# YTN1-POWER1-RoHS.net
KiCad netlist of a schematic drawn in Altium Designer
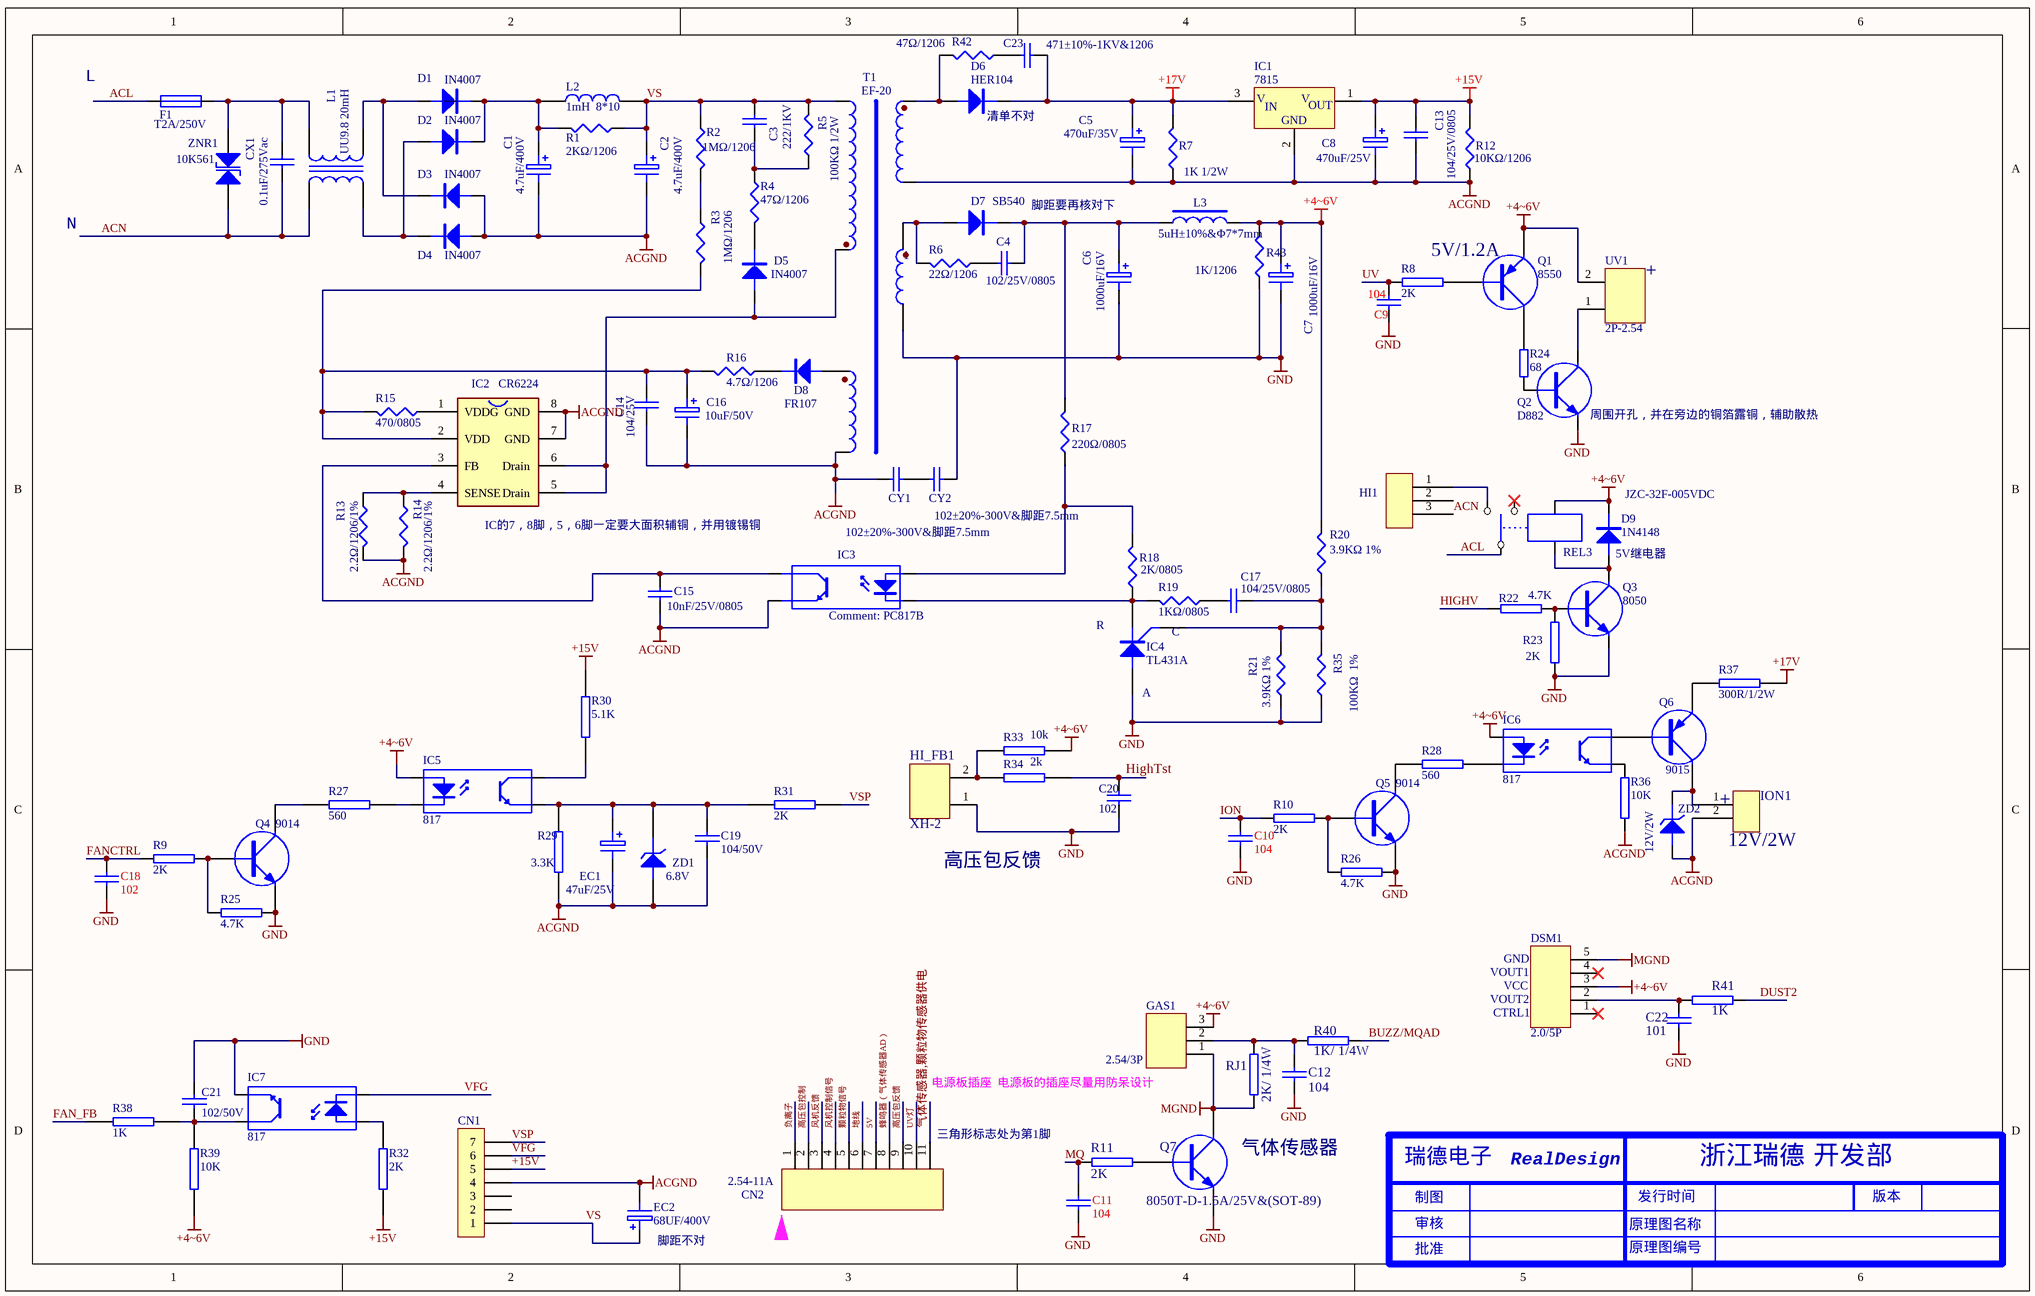
[diagram p0: YTN1-POWER1-RoHS.schdoc]

(export (version "E")
  (design (tool "Eeschema 10.0.6"))
  (components
    (comp (ref "1") (value "~") (libsource (lib "*") (part "INDUCTOR")))
    (comp (ref "C1") (value "4.7uF/400V") (libsource (lib "*") (part "Pro18.tmp_150uF/400V_45")))
    (comp (ref "C2") (value "4.7uF/400V") (libsource (lib "*") (part "Pro18.tmp_150uF/400V_45")))
    (comp (ref "C3") (value "222/1KV") (libsource (lib "*") (part "Pro18.tmp_103M/50V_42")))
    (comp (ref "C4") (value "102/25V/0805") (libsource (lib "*") (part "Pro18.tmp_104M/50V_1")))
    (comp (ref "C5")
      (value "470uF/35V")
      (footprint "ESR")
      (libsource (lib "*") (part "Pro18.tmp_1KuF/16V_17"))
    )
    (comp (ref "C6")
      (value "1000uF/16V")
      (footprint "ESR")
      (libsource (lib "*") (part "Pro18.tmp_1KuF/16V_17"))
    )
    (comp (ref "C7")
      (value "1000uF/16V")
      (footprint "ESR")
      (libsource (lib "*") (part "Pro18.tmp_1KuF/16V_17"))
    )
    (comp (ref "C8")
      (value "470uF/25V")
      (footprint "ESR")
      (libsource (lib "*") (part "Pro18.tmp_1KuF/16V_17"))
    )
    (comp (ref "C9")
      (value "104")
      (footprint "C104")
      (description "瓷片电容、独石电容")
      (libsource (lib "") (part "CAP_1"))
    )
    (comp (ref "C10")
      (value "104")
      (footprint "C104")
      (description "瓷片电容、独石电容")
      (libsource (lib "") (part "CAP_1"))
    )
    (comp (ref "C11")
      (value "104")
      (footprint "C104")
      (description "瓷片电容、独石电容")
      (libsource (lib "") (part "CAP_1"))
    )
    (comp (ref "C12")
      (value "104")
      (footprint "0805C")
      (description "瓷片电容、独石电容")
      (libsource (lib "") (part "CAP_1"))
    )
    (comp (ref "C13") (value "104/25V/0805") (libsource (lib "*") (part "Pro18.tmp_104M/50V_1")))
    (comp (ref "C14") (value "104/25V") (libsource (lib "*") (part "Pro18.tmp_103M/50V_42")))
    (comp (ref "C15") (value "10nF/25V/0805") (libsource (lib "*") (part "Pro18.tmp_103M/50V_42")))
    (comp (ref "C16") (value "10uF/50V") (libsource (lib "*") (part "Pro18.tmp_100uF/35V_31")))
    (comp (ref "C17") (value "104/25V/0805") (libsource (lib "*") (part "Pro18.tmp_103M/50V_42")))
    (comp (ref "C18")
      (value "102")
      (footprint "C104")
      (description "瓷片电容、独石电容")
      (libsource (lib "") (part "CAP_1"))
    )
    (comp (ref "C19")
      (value "104/50V")
      (footprint "0805C")
      (description "Capacitor")
      (libsource (lib "*") (part "CAP"))
    )
    (comp (ref "C20") (value "102") (footprint "0805C") (libsource (lib "") (part "CAP_1")))
    (comp (ref "C21")
      (value "102/50V")
      (footprint "0805C")
      (description "Capacitor")
      (libsource (lib "*") (part "CAP"))
    )
    (comp (ref "C22")
      (value "101")
      (footprint "0805C")
      (description "瓷片电容、独石电容")
      (libsource (lib "") (part "CAP_1"))
    )
    (comp (ref "C23") (value "471±10%-1KV&1206") (libsource (lib "*") (part "Pro18.tmp_104M/50V_1")))
    (comp (ref "CN1")
      (value "~")
      (footprint "XH-7AW")
      (description "Connector")
      (libsource (lib "*") (part "CON7"))
    )
    (comp (ref "CN2") (value "2.54-11A") (footprint "xh-12aw") (libsource (lib "*") (part "3.96-11A")))
    (comp (ref "CX1") (value "0.1uF/275Vac") (libsource (lib "*") (part "Pro18.tmp_103M/50V_42")))
    (comp (ref "CY1")
      (value "102±20%-300V&脚距7.5mm")
      (footprint "Y-222")
      (description "Capacitor")
      (libsource (lib "*") (part "CAP"))
    )
    (comp (ref "CY2")
      (value "102±20%-300V&脚距7.5mm")
      (footprint "Y-222")
      (description "Capacitor")
      (libsource (lib "*") (part "CAP"))
    )
    (comp (ref "D1") (value "IN4007") (libsource (lib "*") (part "Pro18.tmp_SB1660_20")))
    (comp (ref "D2") (value "IN4007") (libsource (lib "*") (part "Pro18.tmp_SB1660_20")))
    (comp (ref "D3") (value "IN4007") (libsource (lib "*") (part "Pro18.tmp_SB1660_20")))
    (comp (ref "D4") (value "IN4007") (libsource (lib "*") (part "Pro18.tmp_SB1660_20")))
    (comp (ref "D5") (value "IN4007") (libsource (lib "*") (part "Pro18.tmp_SB1660_20")))
    (comp (ref "D6") (value "HER104") (libsource (lib "*") (part "Pro18.tmp_SB1660_20")))
    (comp (ref "D7") (value "SB540") (libsource (lib "*") (part "Pro18.tmp_SB1660_20")))
    (comp (ref "D8") (value "FR107") (libsource (lib "*") (part "Pro18.tmp_SB1660_20")))
    (comp (ref "D9") (value "1N4148") (footprint "D10s-ai") (libsource (lib "*") (part "DIODE")))
    (comp (ref "DSM1") (value "2.0/5P") (footprint "xh-5aw") (libsource (lib "*") (part "3.96-5A")))
    (comp (ref "EC1") (value "47uF/25V") (footprint "47uf25v-ai") (libsource (lib "*") (part "ELECTRO1")))
    (comp (ref "EC2")
      (value "68UF/400V")
      (footprint "68UF")
      (description "电解电容正极为\"1\"号脚")
      (libsource (lib "*") (part "ELECTRO"))
    )
    (comp (ref "F1") (value "T2A/250V") (libsource (lib "*") (part "Pro18.tmp_1.5A/250V_52")))
    (comp (ref "GAS1") (value "2.54/3P") (footprint "xh-3aw") (libsource (lib "*") (part "3.96-3A")))
    (comp (ref "HI1") (value "VH") (footprint "xh-3aw") (libsource (lib "*") (part "3PIN")))
    (comp (ref "HI_FB1") (value "XH-2") (footprint "xh-2aw") (libsource (lib "*") (part "EH-2A")))
    (comp (ref "IC1") (value "7815") (footprint "7805") (libsource (lib "*") (part "78L05")))
    (comp (ref "IC2") (value "CR6224") (libsource (lib "*") (part "CR6228")))
    (comp (ref "IC3") (value "PC817B") (libsource (lib "*") (part "Pro18.tmp_ET1103_16")))
    (comp (ref "IC4") (value "TL431A") (footprint "sip-3p") (libsource (lib "*") (part "SCR")))
    (comp (ref "IC5") (value "817") (footprint "pc817") (libsource (lib "*") (part "OPTOISO1")))
    (comp (ref "IC6") (value "817") (footprint "PC817") (libsource (lib "*") (part "OPTOISO1")))
    (comp (ref "IC7") (value "817") (footprint "PC817") (libsource (lib "*") (part "OPTOISO1")))
    (comp (ref "ION1") (value "~") (footprint "xh-2a") (libsource (lib "*") (part "2PIN")))
    (comp (ref "L1") (value "UU9.8 20mH") (libsource (lib "*") (part "TRANS1")))
    (comp (ref "L2") (value "1mH  8*10") (libsource (lib "*") (part "INDUCTOR")))
    (comp (ref "L3") (value "5uH±10%&Φ7*7mm") (footprint "L6") (libsource (lib "*") (part "INDUCTOR2")))
    (comp (ref "Q1")
      (value "8550")
      (footprint "sot-23")
      (description "PNP Transistor")
      (libsource (lib "") (part "PNP_1"))
    )
    (comp (ref "Q2") (value "D882") (footprint "13003") (libsource (lib "") (part "NPN_2")))
    (comp (ref "Q3") (value "8050") (footprint "sot-23-s-1") (libsource (lib "") (part "NPN_1")))
    (comp (ref "Q4")
      (value "9014")
      (footprint "SOT-23-S")
      (description "晶体管")
      (libsource (lib "*") (part "NPN"))
    )
    (comp (ref "Q5")
      (value "9014")
      (footprint "SOT-23-S")
      (description "晶体管")
      (libsource (lib "*") (part "NPN"))
    )
    (comp (ref "Q6")
      (value "9015")
      (footprint "SOT-23-S")
      (description "晶体管")
      (libsource (lib "*") (part "PNP"))
    )
    (comp (ref "Q7")
      (value "8050T-D-1.5A/25V&(SOT-89)")
      (footprint "SOT-23-S")
      (description "晶体管")
      (libsource (lib "*") (part "NPN"))
    )
    (comp (ref "R1") (value "2KΩ/1206") (libsource (lib "*") (part "Pro18.tmp_10K_13")))
    (comp (ref "R2") (value "1MΩ/1206") (libsource (lib "*") (part "Pro18.tmp_10K_13")))
    (comp (ref "R3") (value "1MΩ/1206") (libsource (lib "*") (part "Pro18.tmp_10K_13")))
    (comp (ref "R4") (value "47Ω/1206") (libsource (lib "*") (part "Pro18.tmp_10K_13")))
    (comp (ref "R5") (value "100KΩ 1/2W") (libsource (lib "*") (part "Pro18.tmp_10K_13")))
    (comp (ref "R6") (value "22Ω/1206") (libsource (lib "*") (part "Pro18.tmp_560R_15")))
    (comp (ref "R7") (value "1K 1/2W") (libsource (lib "*") (part "Pro18.tmp_560R_15")))
    (comp (ref "R8")
      (value "2K")
      (footprint "R400")
      (description "碳膜电阻、氧化膜电阻、线绕电阻、水泥电阻、玻璃釉电阻")
      (libsource (lib "*") (part "R"))
    )
    (comp (ref "R9")
      (value "2K")
      (footprint "0805R-S")
      (description "碳膜电阻、氧化膜电阻、线绕电阻、水泥电阻、玻璃釉电阻")
      (libsource (lib "*") (part "R"))
    )
    (comp (ref "R10")
      (value "2K")
      (footprint "0805R-S")
      (description "碳膜电阻、氧化膜电阻、线绕电阻、水泥电阻、玻璃釉电阻")
      (libsource (lib "*") (part "R"))
    )
    (comp (ref "R11")
      (value "2K")
      (footprint "0805R-S")
      (description "碳膜电阻、氧化膜电阻、线绕电阻、水泥电阻、玻璃釉电阻")
      (libsource (lib "*") (part "R"))
    )
    (comp (ref "R12") (value "10KΩ/1206") (libsource (lib "*") (part "Pro18.tmp_560R_15")))
    (comp (ref "R13") (value "2.2Ω/1206/1%") (libsource (lib "*") (part "Pro18.tmp_10K_13")))
    (comp (ref "R14") (value "2.2Ω/1206/1%") (libsource (lib "*") (part "Pro18.tmp_10K_13")))
    (comp (ref "R15") (value "470/0805") (libsource (lib "*") (part "Pro18.tmp_10K_13")))
    (comp (ref "R16") (value "4.7Ω/1206") (libsource (lib "*") (part "Pro18.tmp_560R_15")))
    (comp (ref "R17") (value "220Ω/0805") (libsource (lib "*") (part "Pro18.tmp_560R_15")))
    (comp (ref "R18") (value "2K/0805") (libsource (lib "*") (part "Pro18.tmp_560R_15")))
    (comp (ref "R19") (value "1KΩ/0805") (libsource (lib "*") (part "Pro18.tmp_560R_15")))
    (comp (ref "R20") (value "3.9KΩ 1%") (libsource (lib "*") (part "Pro18.tmp_560R_15")))
    (comp (ref "R21") (value "3.9KΩ 1%") (libsource (lib "*") (part "Pro18.tmp_560R_15")))
    (comp (ref "R22") (value "4.7K") (footprint "0805r") (libsource (lib "") (part "RES2_1")))
    (comp (ref "R23") (value "2K") (footprint "0805r") (libsource (lib "") (part "RES2_1")))
    (comp (ref "R24") (value "68") (footprint "0805r-s") (libsource (lib "") (part "R_1")))
    (comp (ref "R25")
      (value "4.7K")
      (footprint "0805R-S")
      (description "碳膜电阻、氧化膜电阻、线绕电阻、水泥电阻、玻璃釉电阻")
      (libsource (lib "*") (part "R"))
    )
    (comp (ref "R26")
      (value "4.7K")
      (footprint "0805R-S")
      (description "碳膜电阻、氧化膜电阻、线绕电阻、水泥电阻、玻璃釉电阻")
      (libsource (lib "*") (part "R"))
    )
    (comp (ref "R27") (value "560") (footprint "0805R") (libsource (lib "*") (part "RES2")))
    (comp (ref "R28") (value "560") (footprint "0805R") (libsource (lib "*") (part "RES2")))
    (comp (ref "R29") (value "3.3K") (footprint "0805R") (libsource (lib "*") (part "RES2")))
    (comp (ref "R30") (value "5.1K") (footprint "0805R") (libsource (lib "*") (part "RES2")))
    (comp (ref "R31") (value "2K") (footprint "0805R") (libsource (lib "*") (part "RES2")))
    (comp (ref "R32") (value "2K") (footprint "0805R") (libsource (lib "*") (part "RES2")))
    (comp (ref "R33") (value "10k") (footprint "0805R") (libsource (lib "*") (part "RES2")))
    (comp (ref "R34") (value "2k") (footprint "0805R") (libsource (lib "*") (part "RES2")))
    (comp (ref "R35") (value "100KΩ  1%") (libsource (lib "*") (part "Pro18.tmp_560R_15")))
    (comp (ref "R36")
      (value "10K")
      (footprint "R400")
      (description "碳膜电阻、氧化膜电阻、线绕电阻、水泥电阻、玻璃釉电阻")
      (libsource (lib "*") (part "R"))
    )
    (comp (ref "R37") (value "300R/1/2W") (footprint "0805R") (libsource (lib "*") (part "RES2")))
    (comp (ref "R38") (value "1K") (footprint "0805R") (libsource (lib "*") (part "RES2")))
    (comp (ref "R39") (value "10K") (footprint "0805R") (libsource (lib "*") (part "RES2")))
    (comp (ref "R40")
      (value "1K/ 1/4W")
      (footprint "0805R-S")
      (description "碳膜电阻、氧化膜电阻、线绕电阻、水泥电阻、玻璃釉电阻")
      (libsource (lib "*") (part "R"))
    )
    (comp (ref "R41")
      (value "1K")
      (footprint "0805R-S")
      (description "碳膜电阻、氧化膜电阻、线绕电阻、水泥电阻、玻璃釉电阻")
      (libsource (lib "*") (part "R"))
    )
    (comp (ref "R42") (value "47Ω/1206") (libsource (lib "*") (part "Pro18.tmp_560R_15")))
    (comp (ref "R43") (value "1K/1206") (libsource (lib "*") (part "Pro18.tmp_560R_15")))
    (comp (ref "REL3")
      (value "JZC-32F-005VDC")
      (footprint "HJR-3FF-S-Z")
      (libsource (lib "*") (part "RELAY-SPDT"))
    )
    (comp (ref "RJ1")
      (value "2K/ 1/4W")
      (footprint "0805R-S")
      (description "碳膜电阻、氧化膜电阻、线绕电阻、水泥电阻、玻璃釉电阻")
      (libsource (lib "*") (part "R"))
    )
    (comp (ref "T1") (value "EF-20") (libsource (lib "*") (part "EE-16")))
    (comp (ref "UV1") (value "2P-2.54") (footprint "xh-2aw") (libsource (lib "*") (part "3.96-2A")))
    (comp (ref "ZD1")
      (value "6.8V")
      (footprint "zd400")
      (description "Zener Diode")
      (libsource (lib "*") (part "ZENER3"))
    )
    (comp (ref "ZD2") (value "12V/2W") (footprint "ZD400") (libsource (lib "*") (part "ZD")))
    (comp (ref "ZNR1") (value "10K561") (footprint "y") (libsource (lib "*") (part "MOV")))
  )
  (nets
    (net (code "1") (name "+4~6V") (class "Default")
      (node (ref "C7") (pin "1") (pintype "passive"))
      (node (ref "D9") (pin "K") (pintype "passive"))
      (node (ref "DSM1") (pin "3") (pinfunction "3_3") (pintype "passive"))
      (node (ref "GAS1") (pin "3") (pinfunction "20_3") (pintype "passive"))
      (node (ref "IC5") (pin "A") (pintype "passive"))
      (node (ref "IC6") (pin "A") (pintype "passive"))
      (node (ref "L3") (pin "2") (pinfunction "2_2") (pintype "passive"))
      (node (ref "Q1") (pin "E") (pinfunction "E_E") (pintype "passive"))
      (node (ref "R20") (pin "2") (pintype "passive"))
      (node (ref "R33") (pin "2") (pinfunction "2_2") (pintype "passive"))
      (node (ref "R39") (pin "1") (pinfunction "1_1") (pintype "passive"))
      (node (ref "R43") (pin "2") (pintype "passive"))
      (node (ref "REL3") (pin "5") (pintype "passive"))
      (node (ref "UV1") (pin "2") (pinfunction "2_2") (pintype "passive"))
    )
    (net (code "2") (name "+15V") (class "Default")
      (node (ref "C13") (pin "2") (pintype "passive"))
      (node (ref "C8") (pin "1") (pintype "passive"))
      (node (ref "CN1") (pin "5") (pinfunction "5_5") (pintype "passive"))
      (node (ref "IC1") (pin "1") (pinfunction "VOUT_1") (pintype "passive"))
      (node (ref "R12") (pin "2") (pintype "passive"))
      (node (ref "R30") (pin "2") (pinfunction "2_2") (pintype "passive"))
      (node (ref "R32") (pin "1") (pinfunction "1_1") (pintype "passive"))
    )
    (net (code "3") (name "+17V") (class "Default")
      (node (ref "C23") (pin "1") (pintype "passive"))
      (node (ref "C5") (pin "1") (pintype "passive"))
      (node (ref "D6") (pin "K") (pintype "passive"))
      (node (ref "IC1") (pin "3") (pinfunction "VIN_3") (pintype "passive"))
      (node (ref "R37") (pin "2") (pinfunction "2_2") (pintype "passive"))
      (node (ref "R7") (pin "2") (pintype "passive"))
    )
    (net (code "4") (name "/5V") (class "Default")
      (node (ref "CN2") (pin "7") (pinfunction "7_7") (pintype "passive"))
    )
    (net (code "5") (name "/ACL") (class "Default")
      (node (ref "F1") (pin "1") (pintype "passive"))
      (node (ref "REL3") (pin "3") (pintype "passive"))
    )
    (net (code "6") (name "/ACN") (class "Default")
      (node (ref "CX1") (pin "1") (pintype "passive"))
      (node (ref "HI1") (pin "3") (pintype "passive"))
      (node (ref "L1") (pin "1") (pinfunction "1_1") (pintype "passive"))
      (node (ref "ZNR1") (pin "2") (pinfunction "K_2") (pintype "passive"))
    )
    (net (code "7") (name "/BUZZ{slash}MQAD") (class "Default")
      (node (ref "R40") (pin "2") (pinfunction "2_2") (pintype "passive"))
    )
    (net (code "8") (name "/DUST2") (class "Default")
      (node (ref "R41") (pin "2") (pinfunction "2_2") (pintype "passive"))
    )
    (net (code "9") (name "/FANCTRL") (class "Default")
      (node (ref "C18") (pin "1") (pintype "passive"))
      (node (ref "R9") (pin "2") (pinfunction "2_2") (pintype "passive"))
    )
    (net (code "10") (name "/FAN_FB") (class "Default")
      (node (ref "R38") (pin "2") (pinfunction "2_2") (pintype "passive"))
    )
    (net (code "11") (name "/HIGHV") (class "Default") (node (ref "R22") (pin "2") (pintype "passive")))
    (net (code "12") (name "/HighTst") (class "Default")
      (node (ref "C20") (pin "1") (pintype "passive"))
      (node (ref "R34") (pin "1") (pinfunction "1_1") (pintype "passive"))
    )
    (net (code "13") (name "/ION") (class "Default")
      (node (ref "C10") (pin "1") (pintype "passive"))
      (node (ref "R10") (pin "2") (pinfunction "2_2") (pintype "passive"))
    )
    (net (code "14") (name "/MQ") (class "Default")
      (node (ref "C11") (pin "1") (pintype "passive"))
      (node (ref "R11") (pin "1") (pinfunction "1_1") (pintype "passive"))
    )
    (net (code "15") (name "/UV") (class "Default")
      (node (ref "C9") (pin "1") (pintype "passive"))
      (node (ref "R8") (pin "2") (pinfunction "2_2") (pintype "passive"))
    )
    (net (code "16") (name "/UV灯") (class "Default")
      (node (ref "CN2") (pin "10") (pinfunction "10_10") (pintype "passive"))
    )
    (net (code "17") (name "/VFG") (class "Default")
      (node (ref "CN1") (pin "6") (pinfunction "6_6") (pintype "passive"))
      (node (ref "IC7") (pin "K") (pintype "passive"))
    )
    (net (code "18") (name "/VS") (class "Default")
      (node (ref "C2") (pin "1") (pintype "passive"))
      (node (ref "C3") (pin "2") (pintype "passive"))
      (node (ref "CN1") (pin "1") (pinfunction "1_1") (pintype "passive"))
      (node (ref "EC2") (pin "1") (pintype "passive"))
      (node (ref "L2") (pin "2") (pinfunction "2_2") (pintype "passive"))
      (node (ref "R1") (pin "1") (pintype "passive"))
      (node (ref "R2") (pin "1") (pintype "passive"))
      (node (ref "R5") (pin "2") (pintype "passive"))
      (node (ref "T1") (pin "2") (pinfunction "2_2") (pintype "passive"))
    )
    (net (code "19") (name "/VSP") (class "Default")
      (node (ref "CN1") (pin "7") (pinfunction "7_7") (pintype "passive"))
      (node (ref "R31") (pin "1") (pinfunction "1_1") (pintype "passive"))
    )
    (net (code "20") (name "/地线") (class "Default")
      (node (ref "CN2") (pin "6") (pinfunction "6_6") (pintype "passive"))
    )
    (net (code "21") (name "/气体传感器,颗粒物传感器供电") (class "Default")
      (node (ref "CN2") (pin "11") (pinfunction "11_11") (pintype "passive"))
    )
    (net (code "22") (name "/蜂鸣器（气体传感器AD）") (class "Default")
      (node (ref "CN2") (pin "8") (pinfunction "8_8") (pintype "passive"))
    )
    (net (code "23") (name "/负离子") (class "Default")
      (node (ref "CN2") (pin "1") (pinfunction "1_1") (pintype "passive"))
    )
    (net (code "24") (name "/颗粒物信号") (class "Default")
      (node (ref "CN2") (pin "5") (pinfunction "5_5") (pintype "passive"))
    )
    (net (code "25") (name "/风机反馈") (class "Default")
      (node (ref "CN2") (pin "3") (pinfunction "3_3") (pintype "passive"))
    )
    (net (code "26") (name "/风机控制信号") (class "Default")
      (node (ref "CN2") (pin "4") (pinfunction "4_4") (pintype "passive"))
    )
    (net (code "27") (name "/高压包反馈") (class "Default")
      (node (ref "CN2") (pin "9") (pinfunction "9_9") (pintype "passive"))
    )
    (net (code "28") (name "/高压包控制") (class "Default")
      (node (ref "CN2") (pin "2") (pinfunction "2_2") (pintype "passive"))
    )
    (net (code "29") (name "ACGND") (class "Default")
      (node (ref "C1") (pin "2") (pintype "passive"))
      (node (ref "C13") (pin "1") (pintype "passive"))
      (node (ref "C14") (pin "2") (pintype "passive"))
      (node (ref "C15") (pin "2") (pintype "passive"))
      (node (ref "C16") (pin "2") (pintype "passive"))
      (node (ref "C19") (pin "2") (pinfunction "2_2") (pintype "passive"))
      (node (ref "C2") (pin "2") (pintype "passive"))
      (node (ref "C5") (pin "2") (pintype "passive"))
      (node (ref "C8") (pin "2") (pintype "passive"))
      (node (ref "CN1") (pin "4") (pinfunction "4_4") (pintype "passive"))
      (node (ref "CY1") (pin "1") (pinfunction "1_1") (pintype "passive"))
      (node (ref "D3") (pin "A") (pintype "passive"))
      (node (ref "D4") (pin "A") (pintype "passive"))
      (node (ref "EC1") (pin "2") (pintype "passive"))
      (node (ref "EC2") (pin "2") (pintype "passive"))
      (node (ref "IC1") (pin "2") (pinfunction "GND_2") (pintype "passive"))
      (node (ref "IC2") (pin "7") (pinfunction "GND_7") (pintype "passive"))
      (node (ref "IC2") (pin "8") (pinfunction "GND_8") (pintype "passive"))
      (node (ref "IC3") (pin "E") (pintype "passive"))
      (node (ref "ION1") (pin "2") (pintype "passive"))
      (node (ref "R12") (pin "1") (pintype "passive"))
      (node (ref "R13") (pin "2") (pintype "passive"))
      (node (ref "R14") (pin "2") (pintype "passive"))
      (node (ref "R29") (pin "1") (pinfunction "1_1") (pintype "passive"))
      (node (ref "R36") (pin "2") (pinfunction "2_2") (pintype "passive"))
      (node (ref "R7") (pin "1") (pintype "passive"))
      (node (ref "T1") (pin "5") (pinfunction "5_5") (pintype "passive"))
      (node (ref "T1") (pin "7") (pinfunction "7_7") (pintype "passive"))
      (node (ref "ZD1") (pin "A") (pintype "passive"))
      (node (ref "ZD2") (pin "A") (pintype "passive"))
    )
    (net (code "30") (name "GND") (class "Default")
      (node (ref "1") (pin "1") (pinfunction "1_1") (pintype "passive"))
      (node (ref "C10") (pin "2") (pintype "passive"))
      (node (ref "C11") (pin "2") (pintype "passive"))
      (node (ref "C12") (pin "2") (pintype "passive"))
      (node (ref "C18") (pin "2") (pintype "passive"))
      (node (ref "C20") (pin "2") (pintype "passive"))
      (node (ref "C21") (pin "1") (pinfunction "1_1") (pintype "passive"))
      (node (ref "C22") (pin "2") (pintype "passive"))
      (node (ref "C6") (pin "2") (pintype "passive"))
      (node (ref "C7") (pin "2") (pintype "passive"))
      (node (ref "C9") (pin "2") (pintype "passive"))
      (node (ref "CY2") (pin "2") (pinfunction "2_2") (pintype "passive"))
      (node (ref "HI_FB1") (pin "1") (pinfunction "1_1") (pintype "passive"))
      (node (ref "IC4") (pin "1") (pinfunction "1_1") (pintype "passive"))
      (node (ref "IC7") (pin "E") (pintype "passive"))
      (node (ref "Q2") (pin "E") (pintype "passive"))
      (node (ref "Q3") (pin "E") (pintype "passive"))
      (node (ref "Q4") (pin "E") (pintype "passive"))
      (node (ref "Q5") (pin "E") (pintype "passive"))
      (node (ref "Q7") (pin "E") (pintype "passive"))
      (node (ref "R21") (pin "1") (pintype "passive"))
      (node (ref "R23") (pin "1") (pintype "passive"))
      (node (ref "R25") (pin "1") (pinfunction "1_1") (pintype "passive"))
      (node (ref "R26") (pin "1") (pinfunction "1_1") (pintype "passive"))
      (node (ref "R35") (pin "1") (pintype "passive"))
      (node (ref "R43") (pin "1") (pintype "passive"))
    )
    (net (code "31") (name "MGND") (class "Default")
      (node (ref "DSM1") (pin "5") (pinfunction "5_5") (pintype "passive"))
      (node (ref "GAS1") (pin "1") (pinfunction "1_1") (pintype "passive"))
      (node (ref "Q7") (pin "C") (pintype "passive"))
      (node (ref "RJ1") (pin "2") (pinfunction "2_2") (pintype "passive"))
    )
    (net (code "32") (name "Net-(1-Pad2)") (class "Default")
      (node (ref "1") (pin "2") (pinfunction "2_2") (pintype "passive"))
      (node (ref "D7") (pin "A") (pintype "passive"))
      (node (ref "R6") (pin "2") (pintype "passive"))
    )
    (net (code "33") (name "Net-(C1-Pad1)") (class "Default")
      (node (ref "C1") (pin "1") (pintype "passive"))
      (node (ref "D1") (pin "K") (pintype "passive"))
      (node (ref "D2") (pin "K") (pintype "passive"))
      (node (ref "L2") (pin "1") (pinfunction "1_1") (pintype "passive"))
      (node (ref "R1") (pin "2") (pintype "passive"))
    )
    (net (code "34") (name "Net-(C3-Pad1)") (class "Default")
      (node (ref "C3") (pin "1") (pintype "passive"))
      (node (ref "R4") (pin "1") (pintype "passive"))
      (node (ref "R5") (pin "1") (pintype "passive"))
    )
    (net (code "35") (name "Net-(C4-Pad1)") (class "Default")
      (node (ref "C4") (pin "1") (pintype "passive"))
      (node (ref "C6") (pin "1") (pintype "passive"))
      (node (ref "D7") (pin "K") (pintype "passive"))
      (node (ref "L3") (pin "1") (pinfunction "1_1") (pintype "passive"))
      (node (ref "R17") (pin "2") (pintype "passive"))
    )
    (net (code "36") (name "Net-(C4-Pad2)") (class "Default")
      (node (ref "C4") (pin "2") (pintype "passive"))
      (node (ref "R6") (pin "1") (pintype "passive"))
    )
    (net (code "37") (name "Net-(C12-Pad1)") (class "Default")
      (node (ref "C12") (pin "1") (pintype "passive"))
      (node (ref "GAS1") (pin "2") (pinfunction "2_2") (pintype "passive"))
      (node (ref "R40") (pin "1") (pinfunction "1_1") (pintype "passive"))
      (node (ref "RJ1") (pin "1") (pinfunction "1_1") (pintype "passive"))
    )
    (net (code "38") (name "Net-(C17-Pad1)") (class "Default")
      (node (ref "C17") (pin "1") (pintype "passive"))
      (node (ref "R19") (pin "1") (pintype "passive"))
    )
    (net (code "39") (name "Net-(C17-Pad2)") (class "Default")
      (node (ref "C17") (pin "2") (pintype "passive"))
      (node (ref "IC4") (pin "3") (pinfunction "3_3") (pintype "passive"))
      (node (ref "R20") (pin "1") (pintype "passive"))
      (node (ref "R21") (pin "2") (pintype "passive"))
      (node (ref "R35") (pin "2") (pintype "passive"))
    )
    (net (code "40") (name "Net-(C19-Pad1)") (class "Default")
      (node (ref "C19") (pin "1") (pinfunction "1_1") (pintype "passive"))
      (node (ref "EC1") (pin "1") (pintype "passive"))
      (node (ref "IC5") (pin "E") (pintype "passive"))
      (node (ref "R29") (pin "2") (pinfunction "2_2") (pintype "passive"))
      (node (ref "R31") (pin "2") (pinfunction "2_2") (pintype "passive"))
      (node (ref "ZD1") (pin "K") (pintype "passive"))
    )
    (net (code "41") (name "Net-(C21-Pad2)") (class "Default")
      (node (ref "C21") (pin "2") (pinfunction "2_2") (pintype "passive"))
      (node (ref "IC7") (pin "C") (pintype "passive"))
      (node (ref "R38") (pin "1") (pinfunction "1_1") (pintype "passive"))
      (node (ref "R39") (pin "2") (pinfunction "2_2") (pintype "passive"))
    )
    (net (code "42") (name "Net-(C22-Pad1)") (class "Default")
      (node (ref "C22") (pin "1") (pintype "passive"))
      (node (ref "DSM1") (pin "2") (pinfunction "2_2") (pintype "passive"))
      (node (ref "R41") (pin "1") (pinfunction "1_1") (pintype "passive"))
    )
    (net (code "43") (name "Net-(C23-Pad2)") (class "Default")
      (node (ref "C23") (pin "2") (pintype "passive"))
      (node (ref "R42") (pin "1") (pintype "passive"))
    )
    (net (code "44") (name "Net-(CY1-Pad2)") (class "Default")
      (node (ref "CY1") (pin "2") (pinfunction "2_2") (pintype "passive"))
      (node (ref "CY2") (pin "1") (pinfunction "1_1") (pintype "passive"))
    )
    (net (code "45") (name "Net-(D1-PadA)") (class "Default")
      (node (ref "D1") (pin "A") (pintype "passive"))
      (node (ref "D3") (pin "K") (pintype "passive"))
      (node (ref "L1") (pin "4") (pinfunction "4_4") (pintype "passive"))
    )
    (net (code "46") (name "Net-(D2-PadA)") (class "Default")
      (node (ref "D2") (pin "A") (pintype "passive"))
      (node (ref "D4") (pin "K") (pintype "passive"))
      (node (ref "L1") (pin "3") (pinfunction "3_3") (pintype "passive"))
    )
    (net (code "47") (name "Net-(D5-PadA)") (class "Default")
      (node (ref "D5") (pin "A") (pintype "passive"))
      (node (ref "IC2") (pin "5") (pinfunction "Drain_5") (pintype "passive"))
      (node (ref "IC2") (pin "6") (pinfunction "Drain_6") (pintype "passive"))
      (node (ref "T1") (pin "3") (pinfunction "3_3") (pintype "passive"))
    )
    (net (code "48") (name "Net-(D5-PadK)") (class "Default")
      (node (ref "D5") (pin "K") (pintype "passive"))
      (node (ref "R4") (pin "2") (pintype "passive"))
    )
    (net (code "49") (name "Net-(D6-PadA)") (class "Default")
      (node (ref "D6") (pin "A") (pintype "passive"))
      (node (ref "R42") (pin "2") (pintype "passive"))
      (node (ref "T1") (pin "6") (pinfunction "6_6") (pintype "passive"))
    )
    (net (code "50") (name "Net-(D8-PadA)") (class "Default")
      (node (ref "D8") (pin "A") (pintype "passive"))
      (node (ref "T1") (pin "4") (pinfunction "4_4") (pintype "passive"))
    )
    (net (code "51") (name "Net-(D8-PadK)") (class "Default")
      (node (ref "D8") (pin "K") (pintype "passive"))
      (node (ref "R16") (pin "1") (pintype "passive"))
    )
    (net (code "52") (name "Net-(D9-PadA)") (class "Default")
      (node (ref "D9") (pin "A") (pintype "passive"))
      (node (ref "Q3") (pin "C") (pintype "passive"))
      (node (ref "REL3") (pin "2") (pintype "passive"))
    )
    (net (code "53") (name "Net-(HI1-Pad1)") (class "Default")
      (node (ref "HI1") (pin "1") (pintype "passive"))
      (node (ref "REL3") (pin "4") (pintype "passive"))
    )
    (net (code "54") (name "Net-(HI_FB1-Pad2)") (class "Default")
      (node (ref "HI_FB1") (pin "2") (pinfunction "2_2") (pintype "passive"))
      (node (ref "R33") (pin "1") (pinfunction "1_1") (pintype "passive"))
      (node (ref "R34") (pin "2") (pinfunction "2_2") (pintype "passive"))
    )
    (net (code "55") (name "Net-(IC2-FB)") (class "Default")
      (node (ref "C15") (pin "1") (pintype "passive"))
      (node (ref "IC2") (pin "3") (pinfunction "FB_3") (pintype "passive"))
      (node (ref "IC3") (pin "C") (pintype "passive"))
    )
    (net (code "56") (name "Net-(IC2-SENSE)") (class "Default")
      (node (ref "IC2") (pin "4") (pinfunction "SENSE_4") (pintype "passive"))
      (node (ref "R13") (pin "1") (pintype "passive"))
      (node (ref "R14") (pin "1") (pintype "passive"))
    )
    (net (code "57") (name "Net-(IC2-VDD)") (class "Default")
      (node (ref "C14") (pin "1") (pintype "passive"))
      (node (ref "C16") (pin "1") (pintype "passive"))
      (node (ref "IC2") (pin "2") (pinfunction "VDD_2") (pintype "passive"))
      (node (ref "R15") (pin "2") (pintype "passive"))
      (node (ref "R16") (pin "2") (pintype "passive"))
      (node (ref "R3") (pin "2") (pintype "passive"))
    )
    (net (code "58") (name "Net-(IC2-VDDG)") (class "Default")
      (node (ref "IC2") (pin "1") (pinfunction "VDDG_1") (pintype "passive"))
      (node (ref "R15") (pin "1") (pintype "passive"))
    )
    (net (code "59") (name "Net-(IC3-PadA)") (class "Default")
      (node (ref "IC3") (pin "A") (pintype "passive"))
      (node (ref "R17") (pin "1") (pintype "passive"))
      (node (ref "R18") (pin "2") (pintype "passive"))
    )
    (net (code "60") (name "Net-(IC3-PadK)") (class "Default")
      (node (ref "IC3") (pin "K") (pintype "passive"))
      (node (ref "IC4") (pin "2") (pinfunction "2_2") (pintype "passive"))
      (node (ref "R18") (pin "1") (pintype "passive"))
      (node (ref "R19") (pin "2") (pintype "passive"))
    )
    (net (code "61") (name "Net-(IC5-PadC)") (class "Default")
      (node (ref "IC5") (pin "C") (pintype "passive"))
      (node (ref "R30") (pin "1") (pinfunction "1_1") (pintype "passive"))
    )
    (net (code "62") (name "Net-(IC5-PadK)") (class "Default")
      (node (ref "IC5") (pin "K") (pintype "passive"))
      (node (ref "R27") (pin "1") (pinfunction "1_1") (pintype "passive"))
    )
    (net (code "63") (name "Net-(IC6-PadC)") (class "Default")
      (node (ref "IC6") (pin "C") (pintype "passive"))
      (node (ref "Q6") (pin "B") (pintype "passive"))
    )
    (net (code "64") (name "Net-(IC6-PadE)") (class "Default")
      (node (ref "IC6") (pin "E") (pintype "passive"))
      (node (ref "R36") (pin "1") (pinfunction "1_1") (pintype "passive"))
    )
    (net (code "65") (name "Net-(IC6-PadK)") (class "Default")
      (node (ref "IC6") (pin "K") (pintype "passive"))
      (node (ref "R28") (pin "1") (pinfunction "1_1") (pintype "passive"))
    )
    (net (code "66") (name "Net-(IC7-PadA)") (class "Default")
      (node (ref "IC7") (pin "A") (pintype "passive"))
      (node (ref "R32") (pin "2") (pinfunction "2_2") (pintype "passive"))
    )
    (net (code "67") (name "Net-(ION1-Pad1)") (class "Default")
      (node (ref "ION1") (pin "1") (pintype "passive"))
      (node (ref "Q6") (pin "C") (pintype "passive"))
      (node (ref "ZD2") (pin "K") (pintype "passive"))
    )
    (net (code "68") (name "Net-(Q1-PadB)") (class "Default")
      (node (ref "Q1") (pin "B") (pinfunction "B_B") (pintype "passive"))
      (node (ref "R8") (pin "1") (pinfunction "1_1") (pintype "passive"))
    )
    (net (code "69") (name "Net-(Q1-PadC)") (class "Default")
      (node (ref "Q1") (pin "C") (pinfunction "C_C") (pintype "passive"))
      (node (ref "R24") (pin "1") (pinfunction "1_1") (pintype "passive"))
    )
    (net (code "70") (name "Net-(Q2-PadB)") (class "Default")
      (node (ref "Q2") (pin "B") (pintype "passive"))
      (node (ref "R24") (pin "2") (pinfunction "2_2") (pintype "passive"))
    )
    (net (code "71") (name "Net-(Q2-PadC)") (class "Default")
      (node (ref "Q2") (pin "C") (pintype "passive"))
      (node (ref "UV1") (pin "1") (pinfunction "1_1") (pintype "passive"))
    )
    (net (code "72") (name "Net-(Q3-PadB)") (class "Default")
      (node (ref "Q3") (pin "B") (pintype "passive"))
      (node (ref "R22") (pin "1") (pintype "passive"))
      (node (ref "R23") (pin "2") (pintype "passive"))
    )
    (net (code "73") (name "Net-(Q4-PadB)") (class "Default")
      (node (ref "Q4") (pin "B") (pintype "passive"))
      (node (ref "R25") (pin "2") (pinfunction "2_2") (pintype "passive"))
      (node (ref "R9") (pin "1") (pinfunction "1_1") (pintype "passive"))
    )
    (net (code "74") (name "Net-(Q4-PadC)") (class "Default")
      (node (ref "Q4") (pin "C") (pintype "passive"))
      (node (ref "R27") (pin "2") (pinfunction "2_2") (pintype "passive"))
    )
    (net (code "75") (name "Net-(Q5-PadB)") (class "Default")
      (node (ref "Q5") (pin "B") (pintype "passive"))
      (node (ref "R10") (pin "1") (pinfunction "1_1") (pintype "passive"))
      (node (ref "R26") (pin "2") (pinfunction "2_2") (pintype "passive"))
    )
    (net (code "76") (name "Net-(Q5-PadC)") (class "Default")
      (node (ref "Q5") (pin "C") (pintype "passive"))
      (node (ref "R28") (pin "2") (pinfunction "2_2") (pintype "passive"))
    )
    (net (code "77") (name "Net-(Q6-PadE)") (class "Default")
      (node (ref "Q6") (pin "E") (pintype "passive"))
      (node (ref "R37") (pin "1") (pinfunction "1_1") (pintype "passive"))
    )
    (net (code "78") (name "Net-(Q7-PadB)") (class "Default")
      (node (ref "Q7") (pin "B") (pintype "passive"))
      (node (ref "R11") (pin "2") (pinfunction "2_2") (pintype "passive"))
    )
    (net (code "79") (name "Net-(R2-Pad2)") (class "Default")
      (node (ref "R2") (pin "2") (pintype "passive"))
      (node (ref "R3") (pin "1") (pintype "passive"))
    )
    (net (code "80") (name "Net-(ZNR1-A)") (class "Default")
      (node (ref "CX1") (pin "2") (pintype "passive"))
      (node (ref "F1") (pin "2") (pintype "passive"))
      (node (ref "L1") (pin "2") (pinfunction "2_2") (pintype "passive"))
      (node (ref "ZNR1") (pin "1") (pinfunction "A_1") (pintype "passive"))
    )
    (net (code "81") (name "unconnected-(CN1-Pad2)") (class "Default")
      (node (ref "CN1") (pin "2") (pinfunction "2_2") (pintype "passive"))
    )
    (net (code "82") (name "unconnected-(CN1-Pad3)") (class "Default")
      (node (ref "CN1") (pin "3") (pinfunction "3_3") (pintype "passive"))
    )
    (net (code "83") (name "unconnected-(DSM1-Pad1)") (class "Default")
      (node (ref "DSM1") (pin "1") (pinfunction "1_1") (pintype "passive+no_connect"))
    )
    (net (code "84") (name "unconnected-(DSM1-Pad4)") (class "Default")
      (node (ref "DSM1") (pin "4") (pinfunction "4_4") (pintype "passive+no_connect"))
    )
    (net (code "85") (name "unconnected-(HI1-Pad2)") (class "Default")
      (node (ref "HI1") (pin "2") (pintype "passive"))
    )
    (net (code "86") (name "unconnected-(REL3-Pad1)") (class "Default")
      (node (ref "REL3") (pin "1") (pintype "passive+no_connect"))
    )
  )
)
